# ATtiny_LED_badge.net
KiCad netlist of a schematic drawn in EAGLE
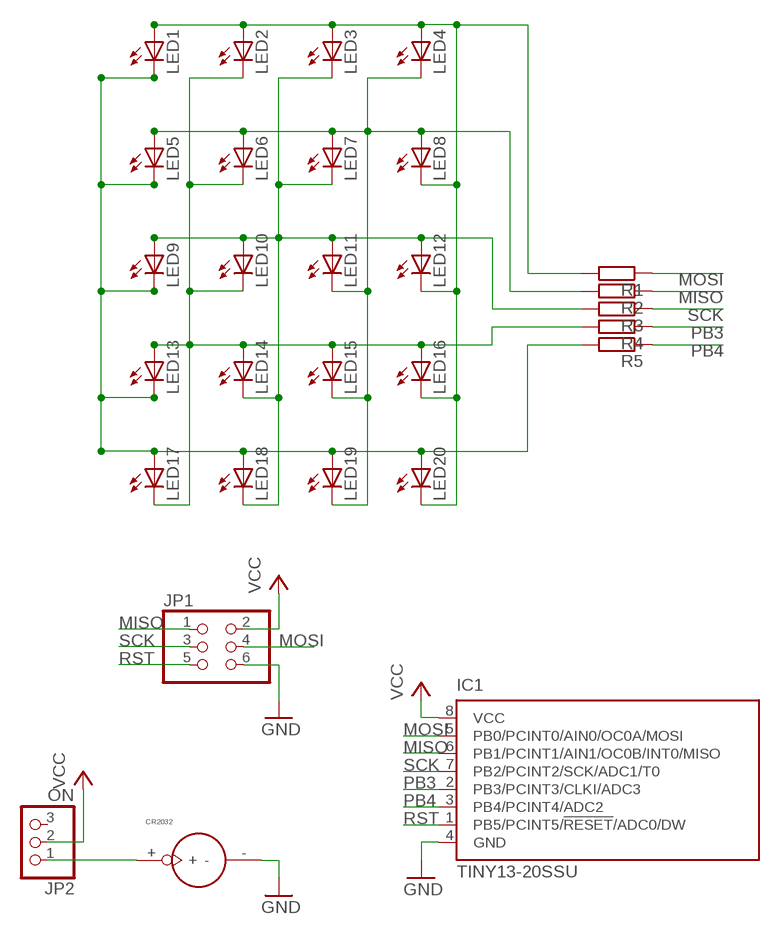
[diagram p0: schematic, sheet 1]

(export (version "E")
  (design (tool "Eeschema 10.0.6"))
  (components
    (comp (ref "CR2032")
      (value "BATTERY_1236_C")
      (footprint "eagle-import:BATTERY_1236_C")
      (libsource (lib "eagle-import") (part "BATTERY_1236_C"))
    )
    (comp (ref "IC1")
      (value "TINY13-20SSU")
      (footprint "eagle-import:8S1")
      (fields (field (name "MPN") "ATTINY13-20SSU"))
      (libsource (lib "eagle-import") (part "TINY13SSU-20"))
    )
    (comp (ref "JP1")
      (value "PINHD-2X3")
      (footprint "eagle-import:2X03")
      (libsource (lib "eagle-import") (part "PINHD-2X3"))
    )
    (comp (ref "JP2")
      (value "ON")
      (footprint "eagle-import:1X03")
      (libsource (lib "eagle-import") (part "PINHD-1X3"))
    )
    (comp (ref "LED1")
      (value "LED3MM")
      (footprint "eagle-import:LED3MM")
      (libsource (lib "eagle-import") (part "LED3MM"))
    )
    (comp (ref "LED2")
      (value "LED3MM")
      (footprint "eagle-import:LED3MM")
      (libsource (lib "eagle-import") (part "LED3MM"))
    )
    (comp (ref "LED3")
      (value "LED3MM")
      (footprint "eagle-import:LED3MM")
      (libsource (lib "eagle-import") (part "LED3MM"))
    )
    (comp (ref "LED4")
      (value "LED3MM")
      (footprint "eagle-import:LED3MM")
      (libsource (lib "eagle-import") (part "LED3MM"))
    )
    (comp (ref "LED5")
      (value "LED3MM")
      (footprint "eagle-import:LED3MM")
      (libsource (lib "eagle-import") (part "LED3MM"))
    )
    (comp (ref "LED6")
      (value "LED3MM")
      (footprint "eagle-import:LED3MM")
      (libsource (lib "eagle-import") (part "LED3MM"))
    )
    (comp (ref "LED7")
      (value "LED3MM")
      (footprint "eagle-import:LED3MM")
      (libsource (lib "eagle-import") (part "LED3MM"))
    )
    (comp (ref "LED8")
      (value "LED3MM")
      (footprint "eagle-import:LED3MM")
      (libsource (lib "eagle-import") (part "LED3MM"))
    )
    (comp (ref "LED9")
      (value "LED3MM")
      (footprint "eagle-import:LED3MM")
      (libsource (lib "eagle-import") (part "LED3MM"))
    )
    (comp (ref "LED10")
      (value "LED3MM")
      (footprint "eagle-import:LED3MM")
      (libsource (lib "eagle-import") (part "LED3MM"))
    )
    (comp (ref "LED11")
      (value "LED3MM")
      (footprint "eagle-import:LED3MM")
      (libsource (lib "eagle-import") (part "LED3MM"))
    )
    (comp (ref "LED12")
      (value "LED3MM")
      (footprint "eagle-import:LED3MM")
      (libsource (lib "eagle-import") (part "LED3MM"))
    )
    (comp (ref "LED13")
      (value "LED3MM")
      (footprint "eagle-import:LED3MM")
      (libsource (lib "eagle-import") (part "LED3MM"))
    )
    (comp (ref "LED14")
      (value "LED3MM")
      (footprint "eagle-import:LED3MM")
      (libsource (lib "eagle-import") (part "LED3MM"))
    )
    (comp (ref "LED15")
      (value "LED3MM")
      (footprint "eagle-import:LED3MM")
      (libsource (lib "eagle-import") (part "LED3MM"))
    )
    (comp (ref "LED16")
      (value "LED3MM")
      (footprint "eagle-import:LED3MM")
      (libsource (lib "eagle-import") (part "LED3MM"))
    )
    (comp (ref "LED17")
      (value "LED3MM")
      (footprint "eagle-import:LED3MM")
      (libsource (lib "eagle-import") (part "LED3MM"))
    )
    (comp (ref "LED18")
      (value "LED3MM")
      (footprint "eagle-import:LED3MM")
      (libsource (lib "eagle-import") (part "LED3MM"))
    )
    (comp (ref "LED19")
      (value "LED3MM")
      (footprint "eagle-import:LED3MM")
      (libsource (lib "eagle-import") (part "LED3MM"))
    )
    (comp (ref "LED20")
      (value "LED3MM")
      (footprint "eagle-import:LED3MM")
      (libsource (lib "eagle-import") (part "LED3MM"))
    )
    (comp (ref "R1")
      (value "R-EU_0207/7")
      (footprint "eagle-import:0207_7")
      (libsource (lib "eagle-import") (part "R-EU_0207/7"))
    )
    (comp (ref "R2")
      (value "R-EU_0207/7")
      (footprint "eagle-import:0207_7")
      (libsource (lib "eagle-import") (part "R-EU_0207/7"))
    )
    (comp (ref "R3")
      (value "R-EU_0207/7")
      (footprint "eagle-import:0207_7")
      (libsource (lib "eagle-import") (part "R-EU_0207/7"))
    )
    (comp (ref "R4")
      (value "R-EU_0207/7")
      (footprint "eagle-import:0207_7")
      (libsource (lib "eagle-import") (part "R-EU_0207/7"))
    )
    (comp (ref "R5")
      (value "R-EU_0207/7")
      (footprint "eagle-import:0207_7")
      (libsource (lib "eagle-import") (part "R-EU_0207/7"))
    )
  )
  (nets
    (net (code "1") (name "/MISO") (class "Default")
      (node (ref "IC1") (pin "6") (pinfunction "PB1/PCINT1/AIN1/OC0B/INT0/MISO_6") (pintype "bidirectional"))
      (node (ref "JP1") (pin "1") (pinfunction "1_1") (pintype "passive"))
      (node (ref "R2") (pin "1") (pinfunction "1_1") (pintype "passive"))
    )
    (net (code "2") (name "/MOSI") (class "Default")
      (node (ref "IC1") (pin "5") (pinfunction "PB0/PCINT0/AIN0/OC0A/MOSI_5") (pintype "bidirectional"))
      (node (ref "JP1") (pin "4") (pinfunction "4_4") (pintype "passive"))
      (node (ref "R1") (pin "1") (pinfunction "1_1") (pintype "passive"))
    )
    (net (code "3") (name "/PB3") (class "Default")
      (node (ref "IC1") (pin "2") (pinfunction "PB3/PCINT3/CLKI/ADC3_2") (pintype "bidirectional"))
      (node (ref "R4") (pin "1") (pinfunction "1_1") (pintype "passive"))
    )
    (net (code "4") (name "/PB4") (class "Default")
      (node (ref "IC1") (pin "3") (pinfunction "PB4/PCINT4/ADC2_3") (pintype "bidirectional"))
      (node (ref "R5") (pin "1") (pinfunction "1_1") (pintype "passive"))
    )
    (net (code "5") (name "/RST") (class "Default")
      (node (ref "IC1") (pin "1") (pinfunction "PB5/PCINT5/~{RESET}/ADC0/DW_1") (pintype "bidirectional"))
      (node (ref "JP1") (pin "5") (pinfunction "5_5") (pintype "passive"))
    )
    (net (code "6") (name "/SCK") (class "Default")
      (node (ref "IC1") (pin "7") (pinfunction "PB2/PCINT2/SCK/ADC1/T0_7") (pintype "bidirectional"))
      (node (ref "JP1") (pin "3") (pinfunction "3_3") (pintype "passive"))
      (node (ref "R3") (pin "1") (pinfunction "1_1") (pintype "passive"))
    )
    (net (code "7") (name "GND") (class "Default")
      (node (ref "CR2032") (pin "-") (pinfunction "-_-") (pintype "bidirectional"))
      (node (ref "IC1") (pin "4") (pinfunction "GND_4") (pintype "power_in"))
      (node (ref "JP1") (pin "6") (pinfunction "6_6") (pintype "passive"))
    )
    (net (code "8") (name "Net-(CR2032-Pad+)") (class "Default")
      (node (ref "CR2032") (pin "+") (pinfunction "+_+") (pintype "bidirectional"))
      (node (ref "JP2") (pin "1") (pinfunction "1_1") (pintype "passive"))
    )
    (net (code "9") (name "Net-(LED1-C)") (class "Default")
      (node (ref "LED1") (pin "K") (pinfunction "C_K") (pintype "passive"))
      (node (ref "LED13") (pin "K") (pinfunction "C_K") (pintype "passive"))
      (node (ref "LED17") (pin "A") (pinfunction "A_A") (pintype "passive"))
      (node (ref "LED18") (pin "A") (pinfunction "A_A") (pintype "passive"))
      (node (ref "LED19") (pin "A") (pinfunction "A_A") (pintype "passive"))
      (node (ref "LED20") (pin "A") (pinfunction "A_A") (pintype "passive"))
      (node (ref "LED5") (pin "K") (pinfunction "C_K") (pintype "passive"))
      (node (ref "LED9") (pin "K") (pinfunction "C_K") (pintype "passive"))
      (node (ref "R5") (pin "2") (pinfunction "2_2") (pintype "passive"))
    )
    (net (code "10") (name "Net-(LED10-C)") (class "Default")
      (node (ref "LED10") (pin "K") (pinfunction "C_K") (pintype "passive"))
      (node (ref "LED13") (pin "A") (pinfunction "A_A") (pintype "passive"))
      (node (ref "LED14") (pin "A") (pinfunction "A_A") (pintype "passive"))
      (node (ref "LED15") (pin "A") (pinfunction "A_A") (pintype "passive"))
      (node (ref "LED16") (pin "A") (pinfunction "A_A") (pintype "passive"))
      (node (ref "LED17") (pin "K") (pinfunction "C_K") (pintype "passive"))
      (node (ref "LED2") (pin "K") (pinfunction "C_K") (pintype "passive"))
      (node (ref "LED6") (pin "K") (pinfunction "C_K") (pintype "passive"))
      (node (ref "R4") (pin "2") (pinfunction "2_2") (pintype "passive"))
    )
    (net (code "11") (name "Net-(LED11-C)") (class "Default")
      (node (ref "LED11") (pin "K") (pinfunction "C_K") (pintype "passive"))
      (node (ref "LED15") (pin "K") (pinfunction "C_K") (pintype "passive"))
      (node (ref "LED19") (pin "K") (pinfunction "C_K") (pintype "passive"))
      (node (ref "LED4") (pin "K") (pinfunction "C_K") (pintype "passive"))
      (node (ref "LED5") (pin "A") (pinfunction "A_A") (pintype "passive"))
      (node (ref "LED6") (pin "A") (pinfunction "A_A") (pintype "passive"))
      (node (ref "LED7") (pin "A") (pinfunction "A_A") (pintype "passive"))
      (node (ref "LED8") (pin "A") (pinfunction "A_A") (pintype "passive"))
      (node (ref "R2") (pin "2") (pinfunction "2_2") (pintype "passive"))
    )
    (net (code "12") (name "Net-(LED12-C)") (class "Default")
      (node (ref "LED1") (pin "A") (pinfunction "A_A") (pintype "passive"))
      (node (ref "LED12") (pin "K") (pinfunction "C_K") (pintype "passive"))
      (node (ref "LED16") (pin "K") (pinfunction "C_K") (pintype "passive"))
      (node (ref "LED2") (pin "A") (pinfunction "A_A") (pintype "passive"))
      (node (ref "LED20") (pin "K") (pinfunction "C_K") (pintype "passive"))
      (node (ref "LED3") (pin "A") (pinfunction "A_A") (pintype "passive"))
      (node (ref "LED4") (pin "A") (pinfunction "A_A") (pintype "passive"))
      (node (ref "LED8") (pin "K") (pinfunction "C_K") (pintype "passive"))
      (node (ref "R1") (pin "2") (pinfunction "2_2") (pintype "passive"))
    )
    (net (code "13") (name "Net-(LED14-C)") (class "Default")
      (node (ref "LED10") (pin "A") (pinfunction "A_A") (pintype "passive"))
      (node (ref "LED11") (pin "A") (pinfunction "A_A") (pintype "passive"))
      (node (ref "LED12") (pin "A") (pinfunction "A_A") (pintype "passive"))
      (node (ref "LED14") (pin "K") (pinfunction "C_K") (pintype "passive"))
      (node (ref "LED18") (pin "K") (pinfunction "C_K") (pintype "passive"))
      (node (ref "LED3") (pin "K") (pinfunction "C_K") (pintype "passive"))
      (node (ref "LED7") (pin "K") (pinfunction "C_K") (pintype "passive"))
      (node (ref "LED9") (pin "A") (pinfunction "A_A") (pintype "passive"))
      (node (ref "R3") (pin "2") (pinfunction "2_2") (pintype "passive"))
    )
    (net (code "14") (name "VCC") (class "Default")
      (node (ref "IC1") (pin "8") (pinfunction "VCC_8") (pintype "power_in"))
      (node (ref "JP1") (pin "2") (pinfunction "2_2") (pintype "passive"))
      (node (ref "JP2") (pin "2") (pinfunction "2_2") (pintype "passive"))
    )
    (net (code "15") (name "unconnected-(JP2-Pad3)") (class "Default")
      (node (ref "JP2") (pin "3") (pinfunction "3_3") (pintype "passive"))
    )
  )
)
